# TacitusC.net
KiCad netlist of a schematic drawn in EAGLE
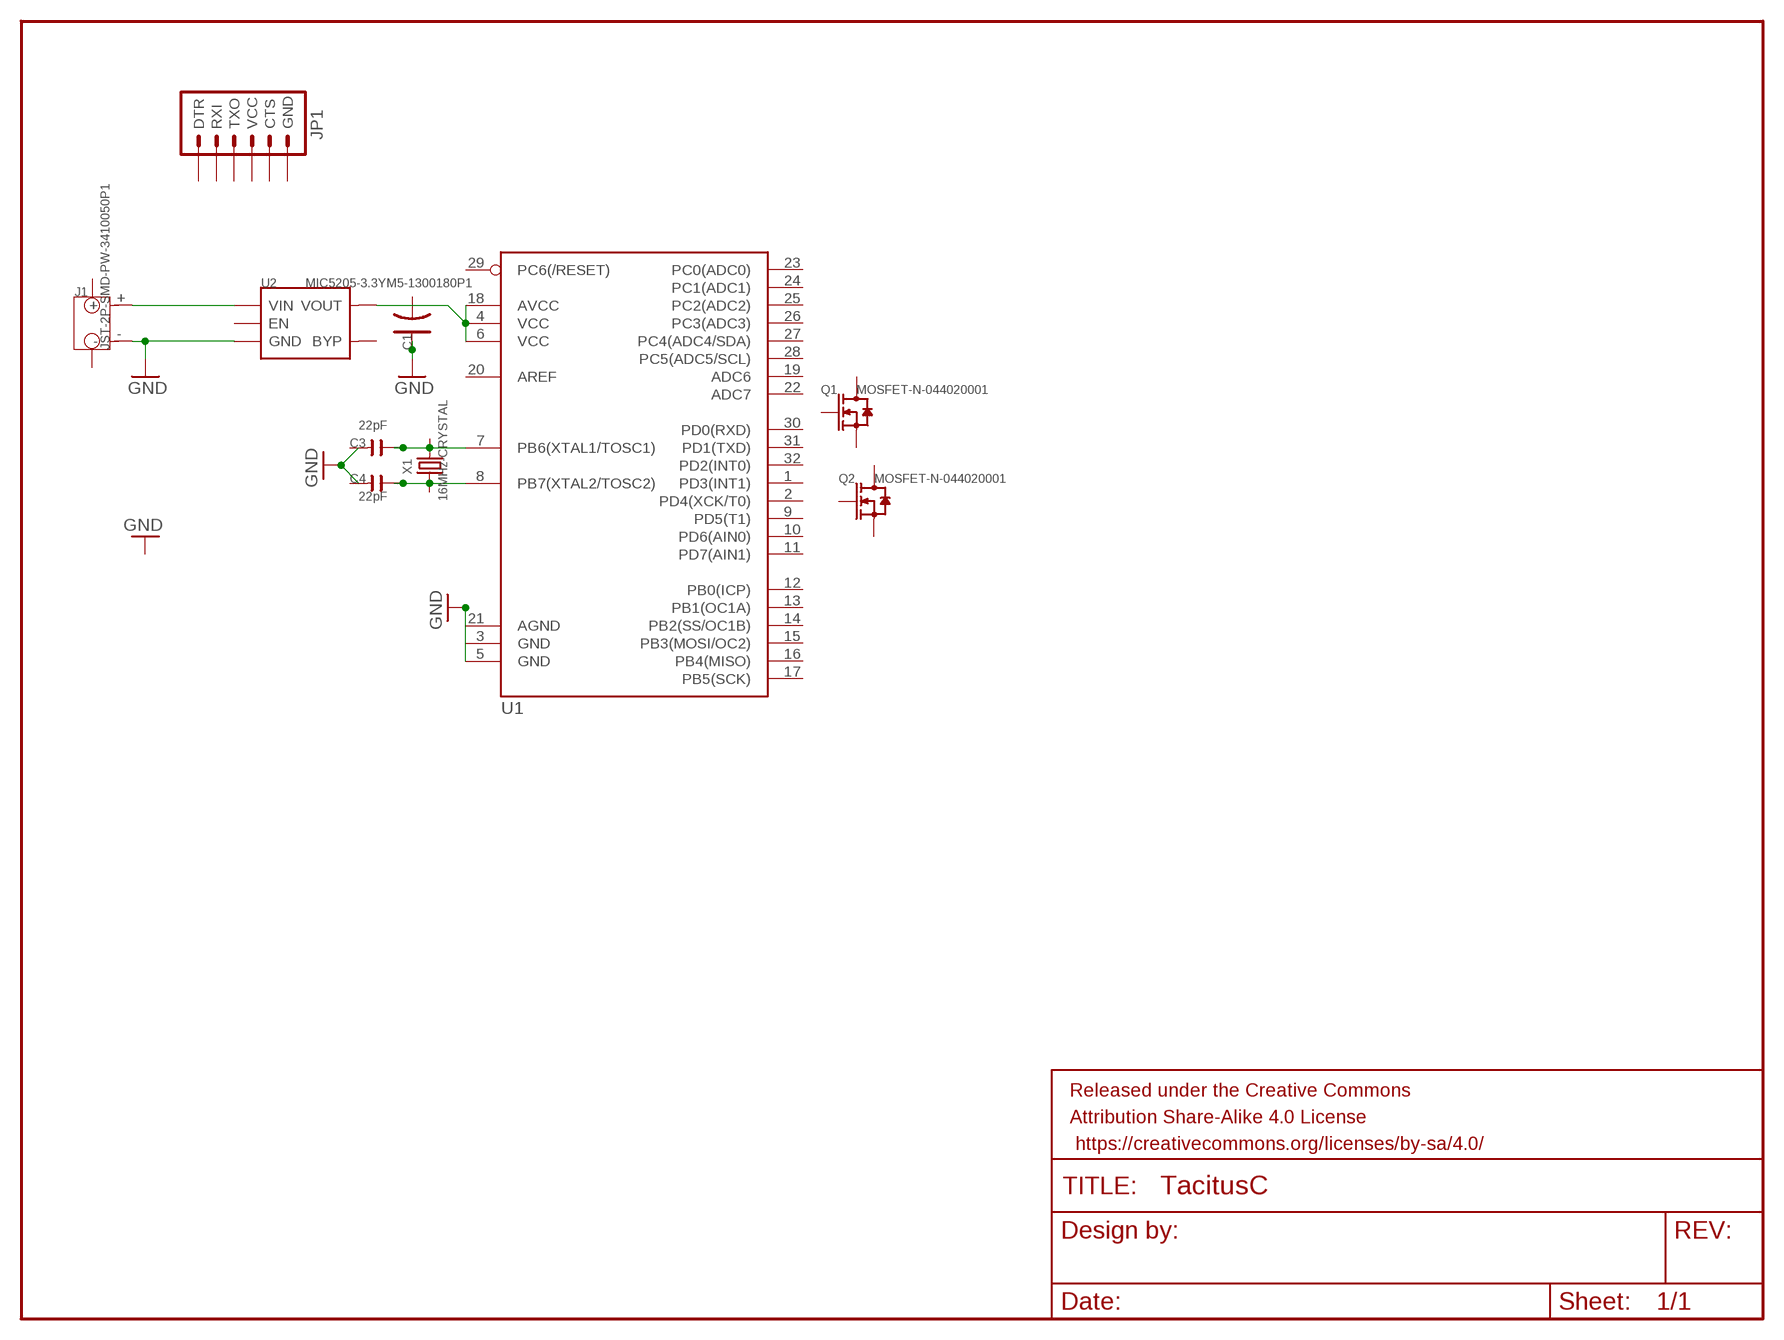
[diagram p0: schematic, sheet 1]

(export (version "E")
  (design (tool "Eeschema 10.0.6"))
  (components
    (comp (ref "C1")
      (value "C-POLAR-A")
      (footprint "eagle-import:AVX-A")
      (libsource (lib "eagle-import") (part "C-POLAR-A"))
    )
    (comp (ref "C3")
      (value "22pF")
      (footprint "eagle-import:C0603")
      (libsource (lib "eagle-import") (part "C-0603"))
    )
    (comp (ref "C4")
      (value "22pF")
      (footprint "eagle-import:C0603")
      (libsource (lib "eagle-import") (part "C-0603"))
    )
    (comp (ref "FRAME1")
      (value "FRAME-LETTER")
      (footprint "eagle-import:CREATIVE_COMMONS")
      (libsource (lib "eagle-import") (part "FRAME-LETTER"))
    )
    (comp (ref "J1")
      (value "JST-2P-SMD-PW-3410050P1")
      (footprint "eagle-import:2P-SMD-2.0-90D")
      (libsource (lib "eagle-import") (part "JST-2P-SMD-PW-3410050P1"))
    )
    (comp (ref "JP1")
      (value "ARDUINO_SERIAL_PROGRAMPTH")
      (footprint "eagle-import:1X06")
      (libsource (lib "eagle-import") (part "ARDUINO_SERIAL_PROGRAMPTH"))
    )
    (comp (ref "Q1")
      (value "MOSFET-N-044020001")
      (footprint "eagle-import:SOT23")
      (libsource (lib "eagle-import") (part "MOSFET-N-044020001"))
    )
    (comp (ref "Q2")
      (value "MOSFET-N-044020001")
      (footprint "eagle-import:SOT23")
      (libsource (lib "eagle-import") (part "MOSFET-N-044020001"))
    )
    (comp (ref "U1")
      (value "ATMEGA328_SMT")
      (footprint "eagle-import:TQFP32-08")
      (libsource (lib "eagle-import") (part "ATMEGA328_SMT"))
    )
    (comp (ref "U2")
      (value "MIC5205-3.3YM5-1300180P1")
      (footprint "eagle-import:SOT23-5")
      (libsource (lib "eagle-import") (part "MIC5205-3.3YM5-1300180P1"))
    )
    (comp (ref "X1")
      (value "16MHz-CRYSTAL")
      (footprint "eagle-import:2P-SMD-5.0X3.2")
      (libsource (lib "eagle-import") (part "CRYSTAL-0500290P1"))
    )
  )
  (nets
    (net (code "1") (name "GND") (class "Default")
      (node (ref "C1") (pin "+") (pinfunction "1_+") (pintype "bidirectional"))
      (node (ref "J1") (pin "-") (pinfunction "-_-") (pintype "bidirectional"))
      (node (ref "U1") (pin "21") (pinfunction "AGND_21") (pintype "bidirectional"))
      (node (ref "U1") (pin "3") (pinfunction "GND_3") (pintype "bidirectional"))
      (node (ref "U1") (pin "5") (pinfunction "GND_5") (pintype "bidirectional"))
      (node (ref "U2") (pin "2") (pinfunction "GND_2") (pintype "bidirectional"))
    )
    (net (code "2") (name "Net-(U1-AVCC)") (class "Default")
      (node (ref "U1") (pin "18") (pinfunction "AVCC_18") (pintype "bidirectional"))
      (node (ref "U1") (pin "4") (pinfunction "VCC_4") (pintype "bidirectional"))
      (node (ref "U1") (pin "6") (pinfunction "VCC_6") (pintype "bidirectional"))
      (node (ref "U2") (pin "5") (pinfunction "VOUT_5") (pintype "bidirectional"))
    )
    (net (code "3") (name "Net-(U1-PB6(XTAL1{slash}TOSC1))") (class "Default")
      (node (ref "C3") (pin "2") (pinfunction "2_2") (pintype "bidirectional"))
      (node (ref "U1") (pin "7") (pinfunction "PB6(XTAL1/TOSC1)_7") (pintype "bidirectional"))
    )
    (net (code "4") (name "Net-(U1-PB7(XTAL2{slash}TOSC2))") (class "Default")
      (node (ref "C4") (pin "2") (pinfunction "2_2") (pintype "bidirectional"))
      (node (ref "U1") (pin "8") (pinfunction "PB7(XTAL2/TOSC2)_8") (pintype "bidirectional"))
    )
    (net (code "5") (name "Net-(U2-VIN)") (class "Default")
      (node (ref "J1") (pin "+") (pinfunction "+_+") (pintype "bidirectional"))
      (node (ref "U2") (pin "1") (pinfunction "VIN_1") (pintype "bidirectional"))
    )
    (net (code "6") (name "unconnected-(C1-2-Pad-)") (class "Default")
      (node (ref "C1") (pin "-") (pinfunction "2_-") (pintype "bidirectional"))
    )
    (net (code "7") (name "unconnected-(C3-Pad1)") (class "Default")
      (node (ref "C3") (pin "1") (pinfunction "1_1") (pintype "bidirectional"))
    )
    (net (code "8") (name "unconnected-(C4-Pad1)") (class "Default")
      (node (ref "C4") (pin "1") (pinfunction "1_1") (pintype "bidirectional"))
    )
    (net (code "9") (name "unconnected-(J1-Pad3)") (class "Default")
      (node (ref "J1") (pin "3") (pinfunction "3_3") (pintype "bidirectional"))
    )
    (net (code "10") (name "unconnected-(J1-Pad4)") (class "Default")
      (node (ref "J1") (pin "4") (pinfunction "4_4") (pintype "bidirectional"))
    )
    (net (code "11") (name "unconnected-(JP1-CTS-Pad5)") (class "Default")
      (node (ref "JP1") (pin "5") (pinfunction "CTS_5") (pintype "passive"))
    )
    (net (code "12") (name "unconnected-(JP1-DTR-Pad1)") (class "Default")
      (node (ref "JP1") (pin "1") (pinfunction "DTR_1") (pintype "passive"))
    )
    (net (code "13") (name "unconnected-(JP1-GND-Pad6)") (class "Default")
      (node (ref "JP1") (pin "6") (pinfunction "GND_6") (pintype "passive"))
    )
    (net (code "14") (name "unconnected-(JP1-RXI-Pad2)") (class "Default")
      (node (ref "JP1") (pin "2") (pinfunction "RXI_2") (pintype "passive"))
    )
    (net (code "15") (name "unconnected-(JP1-TXO-Pad3)") (class "Default")
      (node (ref "JP1") (pin "3") (pinfunction "TXO_3") (pintype "passive"))
    )
    (net (code "16") (name "unconnected-(JP1-VCC-Pad4)") (class "Default")
      (node (ref "JP1") (pin "4") (pinfunction "VCC_4") (pintype "passive"))
    )
    (net (code "17") (name "unconnected-(Q1-D-Pad3)") (class "Default")
      (node (ref "Q1") (pin "3") (pinfunction "D_3") (pintype "passive"))
    )
    (net (code "18") (name "unconnected-(Q1-G-Pad1)") (class "Default")
      (node (ref "Q1") (pin "1") (pinfunction "G_1") (pintype "passive"))
    )
    (net (code "19") (name "unconnected-(Q1-S-Pad2)") (class "Default")
      (node (ref "Q1") (pin "2") (pinfunction "S_2") (pintype "passive"))
    )
    (net (code "20") (name "unconnected-(Q2-D-Pad3)") (class "Default")
      (node (ref "Q2") (pin "3") (pinfunction "D_3") (pintype "passive"))
    )
    (net (code "21") (name "unconnected-(Q2-G-Pad1)") (class "Default")
      (node (ref "Q2") (pin "1") (pinfunction "G_1") (pintype "passive"))
    )
    (net (code "22") (name "unconnected-(Q2-S-Pad2)") (class "Default")
      (node (ref "Q2") (pin "2") (pinfunction "S_2") (pintype "passive"))
    )
    (net (code "23") (name "unconnected-(U1-ADC6-Pad19)") (class "Default")
      (node (ref "U1") (pin "19") (pinfunction "ADC6_19") (pintype "bidirectional"))
    )
    (net (code "24") (name "unconnected-(U1-ADC7-Pad22)") (class "Default")
      (node (ref "U1") (pin "22") (pinfunction "ADC7_22") (pintype "bidirectional"))
    )
    (net (code "25") (name "unconnected-(U1-AREF-Pad20)") (class "Default")
      (node (ref "U1") (pin "20") (pinfunction "AREF_20") (pintype "bidirectional"))
    )
    (net (code "26") (name "unconnected-(U1-PB0(ICP)-Pad12)") (class "Default")
      (node (ref "U1") (pin "12") (pinfunction "PB0(ICP)_12") (pintype "bidirectional"))
    )
    (net (code "27") (name "unconnected-(U1-PB1(OC1A)-Pad13)") (class "Default")
      (node (ref "U1") (pin "13") (pinfunction "PB1(OC1A)_13") (pintype "bidirectional"))
    )
    (net (code "28") (name "unconnected-(U1-PB2(SS{slash}OC1B)-Pad14)") (class "Default")
      (node (ref "U1") (pin "14") (pinfunction "PB2(SS/OC1B)_14") (pintype "bidirectional"))
    )
    (net (code "29") (name "unconnected-(U1-PB3(MOSI{slash}OC2)-Pad15)") (class "Default")
      (node (ref "U1") (pin "15") (pinfunction "PB3(MOSI/OC2)_15") (pintype "bidirectional"))
    )
    (net (code "30") (name "unconnected-(U1-PB4(MISO)-Pad16)") (class "Default")
      (node (ref "U1") (pin "16") (pinfunction "PB4(MISO)_16") (pintype "bidirectional"))
    )
    (net (code "31") (name "unconnected-(U1-PB5(SCK)-Pad17)") (class "Default")
      (node (ref "U1") (pin "17") (pinfunction "PB5(SCK)_17") (pintype "bidirectional"))
    )
    (net (code "32") (name "unconnected-(U1-PC0(ADC0)-Pad23)") (class "Default")
      (node (ref "U1") (pin "23") (pinfunction "PC0(ADC0)_23") (pintype "bidirectional"))
    )
    (net (code "33") (name "unconnected-(U1-PC1(ADC1)-Pad24)") (class "Default")
      (node (ref "U1") (pin "24") (pinfunction "PC1(ADC1)_24") (pintype "bidirectional"))
    )
    (net (code "34") (name "unconnected-(U1-PC2(ADC2)-Pad25)") (class "Default")
      (node (ref "U1") (pin "25") (pinfunction "PC2(ADC2)_25") (pintype "bidirectional"))
    )
    (net (code "35") (name "unconnected-(U1-PC3(ADC3)-Pad26)") (class "Default")
      (node (ref "U1") (pin "26") (pinfunction "PC3(ADC3)_26") (pintype "bidirectional"))
    )
    (net (code "36") (name "unconnected-(U1-PC4(ADC4{slash}SDA)-Pad27)") (class "Default")
      (node (ref "U1") (pin "27") (pinfunction "PC4(ADC4/SDA)_27") (pintype "bidirectional"))
    )
    (net (code "37") (name "unconnected-(U1-PC5(ADC5{slash}SCL)-Pad28)") (class "Default")
      (node (ref "U1") (pin "28") (pinfunction "PC5(ADC5/SCL)_28") (pintype "bidirectional"))
    )
    (net (code "38") (name "unconnected-(U1-PC6({slash}RESET)-Pad29)") (class "Default")
      (node (ref "U1") (pin "29") (pinfunction "PC6(/RESET)_29") (pintype "bidirectional"))
    )
    (net (code "39") (name "unconnected-(U1-PD0(RXD)-Pad30)") (class "Default")
      (node (ref "U1") (pin "30") (pinfunction "PD0(RXD)_30") (pintype "bidirectional"))
    )
    (net (code "40") (name "unconnected-(U1-PD1(TXD)-Pad31)") (class "Default")
      (node (ref "U1") (pin "31") (pinfunction "PD1(TXD)_31") (pintype "bidirectional"))
    )
    (net (code "41") (name "unconnected-(U1-PD2(INT0)-Pad32)") (class "Default")
      (node (ref "U1") (pin "32") (pinfunction "PD2(INT0)_32") (pintype "bidirectional"))
    )
    (net (code "42") (name "unconnected-(U1-PD3(INT1)-Pad1)") (class "Default")
      (node (ref "U1") (pin "1") (pinfunction "PD3(INT1)_1") (pintype "bidirectional"))
    )
    (net (code "43") (name "unconnected-(U1-PD4(XCK{slash}T0)-Pad2)") (class "Default")
      (node (ref "U1") (pin "2") (pinfunction "PD4(XCK/T0)_2") (pintype "bidirectional"))
    )
    (net (code "44") (name "unconnected-(U1-PD5(T1)-Pad9)") (class "Default")
      (node (ref "U1") (pin "9") (pinfunction "PD5(T1)_9") (pintype "bidirectional"))
    )
    (net (code "45") (name "unconnected-(U1-PD6(AIN0)-Pad10)") (class "Default")
      (node (ref "U1") (pin "10") (pinfunction "PD6(AIN0)_10") (pintype "bidirectional"))
    )
    (net (code "46") (name "unconnected-(U1-PD7(AIN1)-Pad11)") (class "Default")
      (node (ref "U1") (pin "11") (pinfunction "PD7(AIN1)_11") (pintype "bidirectional"))
    )
    (net (code "47") (name "unconnected-(U2-BYP-Pad4)") (class "Default")
      (node (ref "U2") (pin "4") (pinfunction "BYP_4") (pintype "bidirectional"))
    )
    (net (code "48") (name "unconnected-(U2-EN-Pad3)") (class "Default")
      (node (ref "U2") (pin "3") (pinfunction "EN_3") (pintype "bidirectional"))
    )
    (net (code "49") (name "unconnected-(X1-Pad1)") (class "Default")
      (node (ref "X1") (pin "1") (pinfunction "1_1") (pintype "passive"))
    )
    (net (code "50") (name "unconnected-(X1-Pad2)") (class "Default")
      (node (ref "X1") (pin "2") (pinfunction "2_2") (pintype "passive"))
    )
  )
)
